# Pi_Block.net
KiCad netlist of a schematic drawn in EAGLE
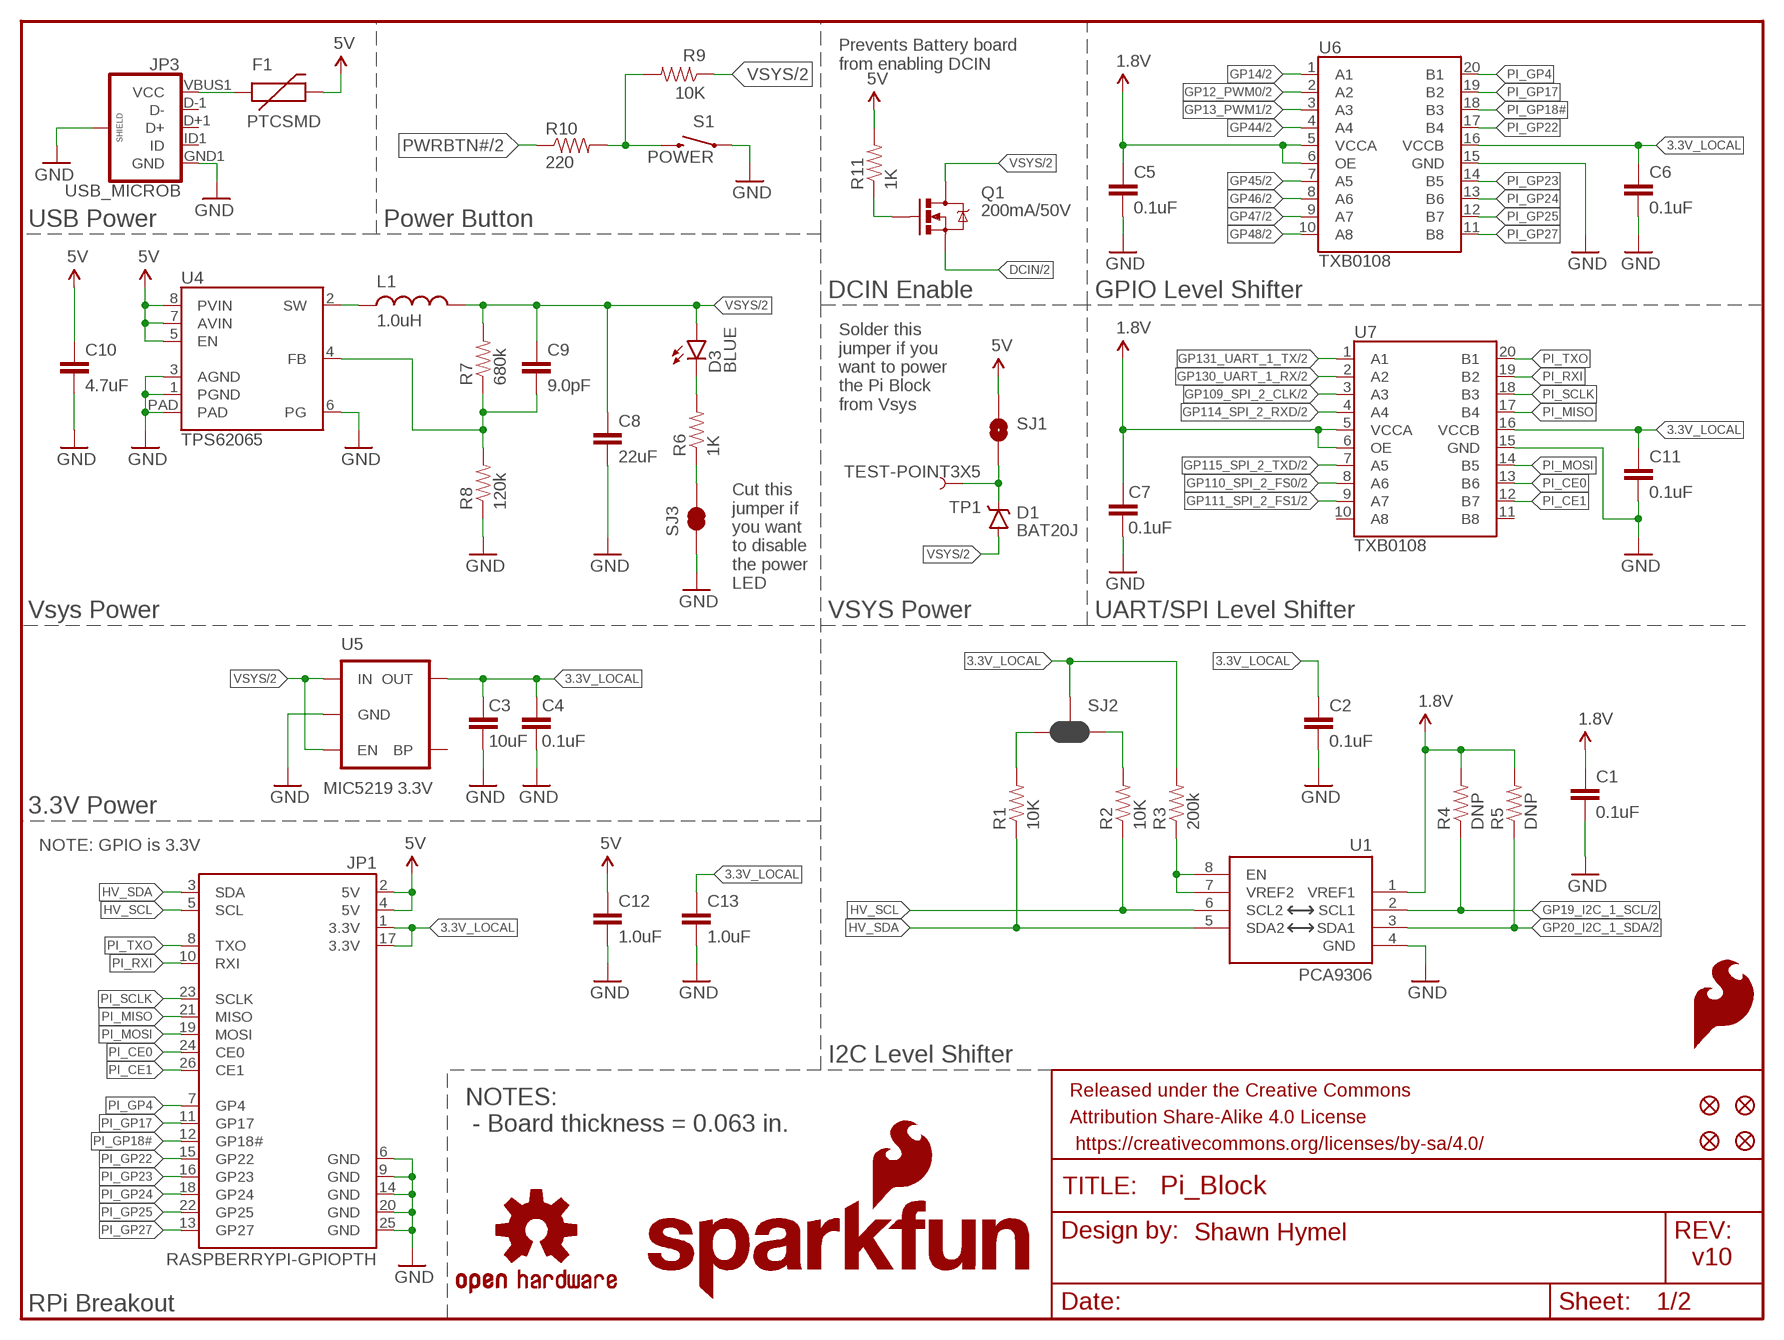
[diagram p0: schematic, sheet 1]
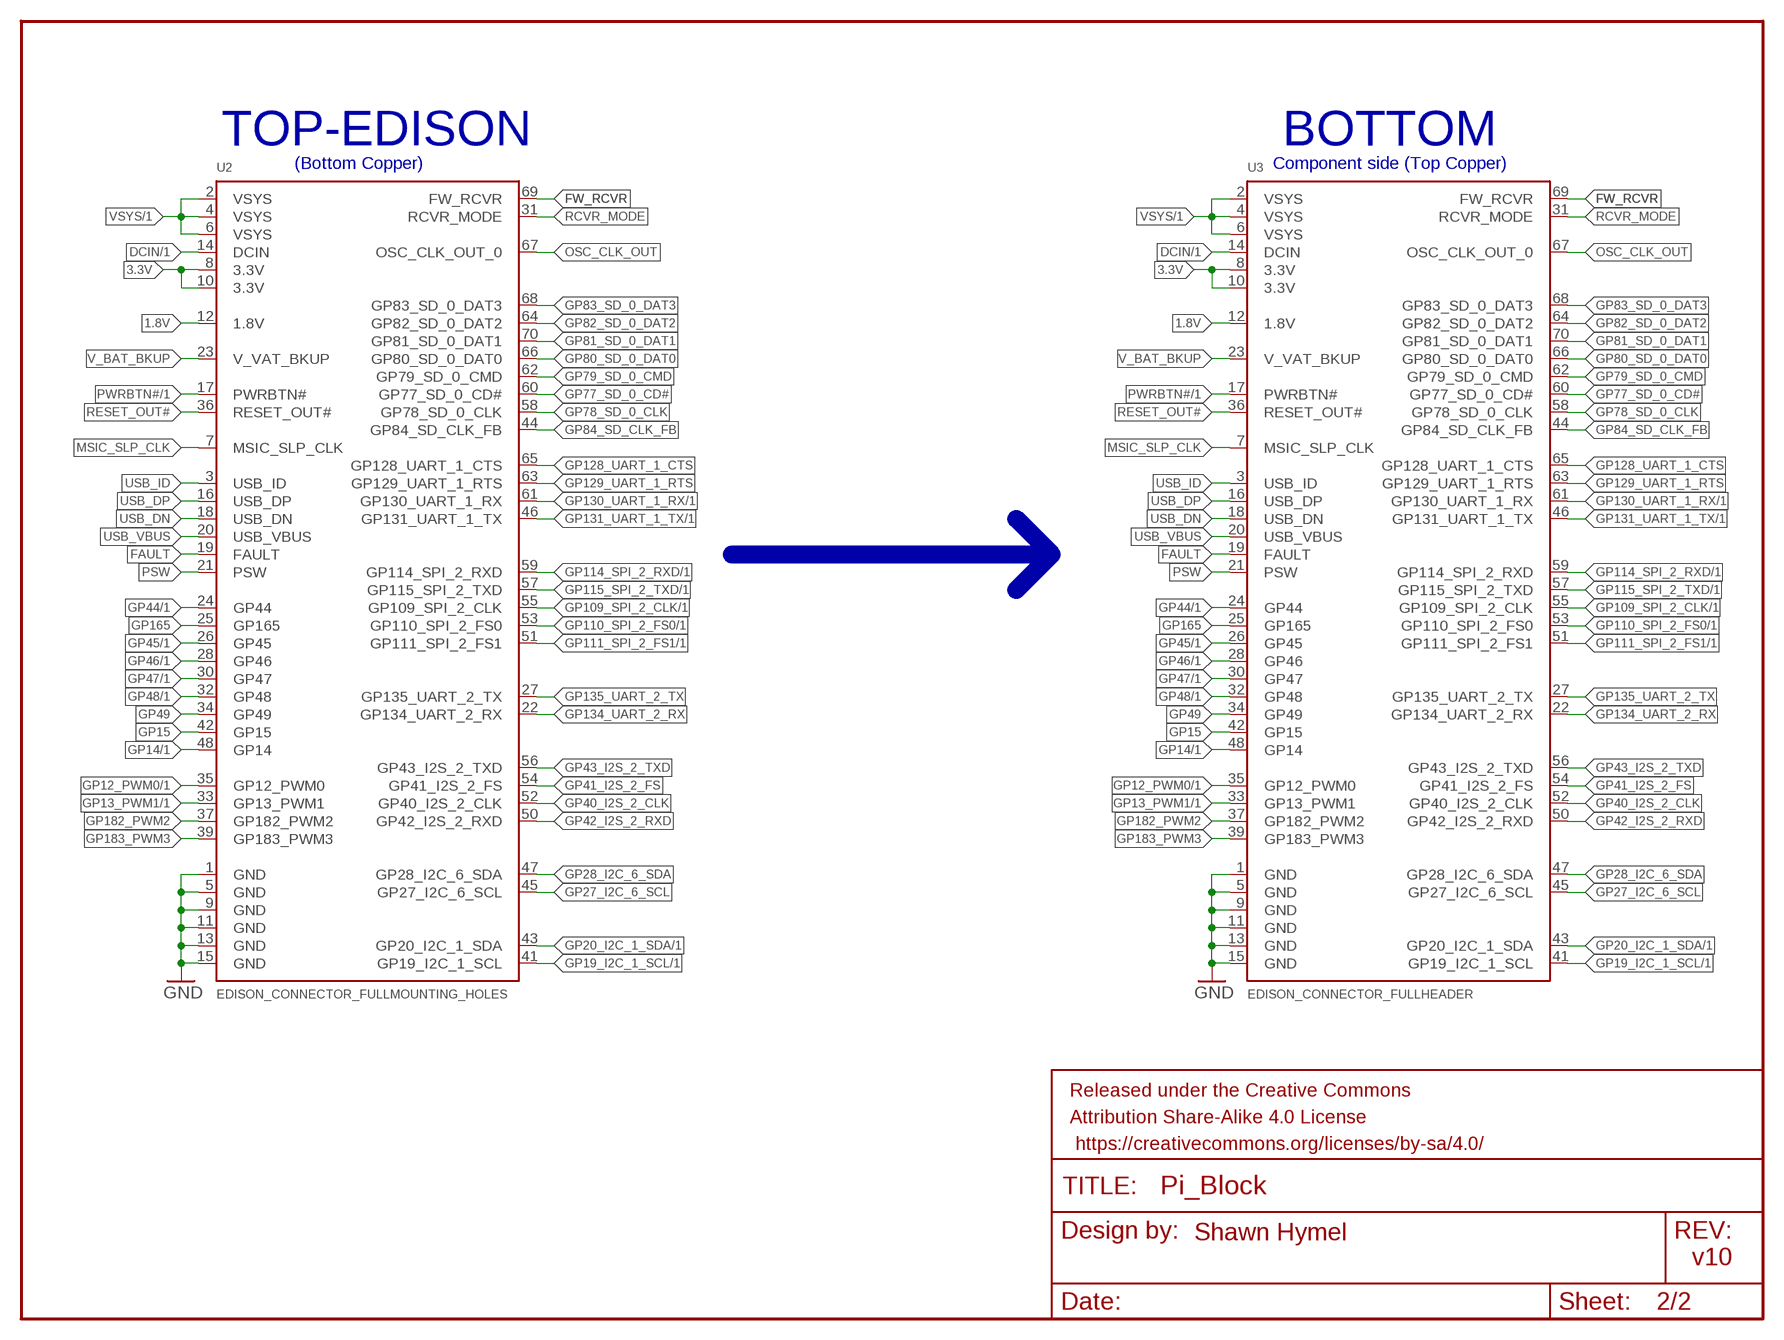
[diagram p1: schematic, sheet 2]

(export (version "E")
  (design (tool "Eeschema 10.0.6"))
  (components
    (comp (ref "FRAME2")
      (value "FRAME-LETTER")
      (footprint "eagle-import:CREATIVE_COMMONS")
      (libsource (lib "eagle-import") (part "FRAME-LETTER"))
    )
    (comp (ref "U2")
      (value "EDISON_CONNECTOR_FULLMOUNTING_HOLES")
      (footprint "eagle-import:EDISON_DAUGHTER")
      (libsource (lib "eagle-import") (part "EDISON_CONNECTOR_FULLMOUNTING_HOLES"))
    )
    (comp (ref "U3")
      (value "EDISON_CONNECTOR_FULLHEADER")
      (footprint "eagle-import:DF40C-70DP-0.4(51)")
      (libsource (lib "eagle-import") (part "EDISON_CONNECTOR_FULLHEADER"))
    )
    (comp (ref "C1")
      (value "0.1uF")
      (footprint "eagle-import:0603-CAP")
      (libsource (lib "eagle-import") (part "0.1UF-25V(+80/-20%)(0603)"))
    )
    (comp (ref "C2")
      (value "0.1uF")
      (footprint "eagle-import:0603-CAP")
      (libsource (lib "eagle-import") (part "0.1UF-25V(+80/-20%)(0603)"))
    )
    (comp (ref "C3")
      (value "10uF")
      (footprint "eagle-import:0805")
      (libsource (lib "eagle-import") (part "CAP0805"))
    )
    (comp (ref "C4")
      (value "0.1uF")
      (footprint "eagle-import:0603-CAP")
      (libsource (lib "eagle-import") (part "0.1UF-25V(+80/-20%)(0603)"))
    )
    (comp (ref "C5")
      (value "0.1uF")
      (footprint "eagle-import:0603-CAP")
      (libsource (lib "eagle-import") (part "0.1UF-25V(+80/-20%)(0603)"))
    )
    (comp (ref "C6")
      (value "0.1uF")
      (footprint "eagle-import:0603-CAP")
      (libsource (lib "eagle-import") (part "0.1UF-25V(+80/-20%)(0603)"))
    )
    (comp (ref "C7")
      (value "0.1uF")
      (footprint "eagle-import:0603-CAP")
      (libsource (lib "eagle-import") (part "0.1UF-25V(+80/-20%)(0603)"))
    )
    (comp (ref "C8")
      (value "22uF")
      (footprint "eagle-import:0805")
      (libsource (lib "eagle-import") (part "22UF-6.3V-20%(0805)"))
    )
    (comp (ref "C9")
      (value "9.0pF")
      (footprint "eagle-import:0603-CAP")
      (libsource (lib "eagle-import") (part "9.0PF-50V-10%(0603)"))
    )
    (comp (ref "C10")
      (value "4.7uF")
      (footprint "eagle-import:0603-CAP")
      (libsource (lib "eagle-import") (part "4.7UF-6.3V-10%(0603)0603"))
    )
    (comp (ref "C11")
      (value "0.1uF")
      (footprint "eagle-import:0603-CAP")
      (libsource (lib "eagle-import") (part "0.1UF-25V(+80/-20%)(0603)"))
    )
    (comp (ref "C12")
      (value "1.0uF")
      (footprint "eagle-import:0603-CAP")
      (libsource (lib "eagle-import") (part "1.0UF-16V-10%(0603)"))
    )
    (comp (ref "C13")
      (value "1.0uF")
      (footprint "eagle-import:0603-CAP")
      (libsource (lib "eagle-import") (part "1.0UF-16V-10%(0603)"))
    )
    (comp (ref "D1")
      (value "BAT20J")
      (footprint "eagle-import:SOD-323")
      (libsource (lib "eagle-import") (part "DIODE-SCHOTTKY-BAT20J"))
    )
    (comp (ref "D3")
      (value "BLUE")
      (footprint "eagle-import:LED-0603")
      (libsource (lib "eagle-import") (part "LED-BLUE0603"))
    )
    (comp (ref "F1")
      (value "PTCSMD")
      (footprint "eagle-import:PTC-1206")
      (libsource (lib "eagle-import") (part "PTCSMD"))
    )
    (comp (ref "FID1")
      (value "FIDUCIAL1X2")
      (footprint "eagle-import:FIDUCIAL-1X2")
      (libsource (lib "eagle-import") (part "FIDUCIAL1X2"))
    )
    (comp (ref "FID2")
      (value "FIDUCIAL1X2")
      (footprint "eagle-import:FIDUCIAL-1X2")
      (libsource (lib "eagle-import") (part "FIDUCIAL1X2"))
    )
    (comp (ref "FID3")
      (value "FIDUCIAL1X2")
      (footprint "eagle-import:FIDUCIAL-1X2")
      (libsource (lib "eagle-import") (part "FIDUCIAL1X2"))
    )
    (comp (ref "FID4")
      (value "FIDUCIAL1X2")
      (footprint "eagle-import:FIDUCIAL-1X2")
      (libsource (lib "eagle-import") (part "FIDUCIAL1X2"))
    )
    (comp (ref "FRAME1")
      (value "FRAME-LETTER")
      (footprint "eagle-import:CREATIVE_COMMONS")
      (libsource (lib "eagle-import") (part "FRAME-LETTER"))
    )
    (comp (ref "FRAME3")
      (value "FRAME-LETTER")
      (footprint "eagle-import:CREATIVE_COMMONS")
      (libsource (lib "eagle-import") (part "FRAME-LETTER"))
    )
    (comp (ref "JP1")
      (value "RASPBERRYPI-GPIOPTH")
      (footprint "eagle-import:2X13-SHROUDED")
      (libsource (lib "eagle-import") (part "RASPBERRYPI-GPIOPTH"))
    )
    (comp (ref "JP3")
      (value "USB_MICROB")
      (footprint "eagle-import:USB-B-MICRO-SMD_V03")
      (libsource (lib "eagle-import") (part "USB_MICROB_PLUGCONN-11752"))
    )
    (comp (ref "L1")
      (value "1.0uH")
      (footprint "eagle-import:INDUCTOR-SRP4020")
      (libsource (lib "eagle-import") (part "INDUCTOR"))
    )
    (comp (ref "LOGO1")
      (value "OSHW-LOGOS")
      (footprint "eagle-import:OSHW-LOGO-S")
      (libsource (lib "eagle-import") (part "OSHW-LOGOS"))
    )
    (comp (ref "LOGO3")
      (value "SFE_LOGO_FLAME.2_INCH")
      (footprint "eagle-import:SFE_LOGO_FLAME_.2")
      (libsource (lib "eagle-import") (part "SFE_LOGO_FLAME.2_INCH"))
    )
    (comp (ref "LOGO4")
      (value "SFE_LOGO_NAME_FLAME.1_INCH")
      (footprint "eagle-import:SFE_LOGO_NAME_FLAME_.1")
      (libsource (lib "eagle-import") (part "SFE_LOGO_NAME_FLAME.1_INCH"))
    )
    (comp (ref "Q1")
      (value "200mA/50V")
      (footprint "eagle-import:SOT23-3")
      (libsource (lib "eagle-import") (part "MOSFET-NCHANNELBSS138"))
    )
    (comp (ref "R1")
      (value "10K")
      (footprint "eagle-import:0603-RES")
      (libsource (lib "eagle-import") (part "10KOHM-1/10W-1%(0603)0603"))
    )
    (comp (ref "R2")
      (value "10K")
      (footprint "eagle-import:0603-RES")
      (libsource (lib "eagle-import") (part "10KOHM-1/10W-1%(0603)0603"))
    )
    (comp (ref "R3")
      (value "200k")
      (footprint "eagle-import:0603-RES")
      (libsource (lib "eagle-import") (part "200KOHM1/10W1%(0603)200K"))
    )
    (comp (ref "R4")
      (value "DNP")
      (footprint "eagle-import:0603-RES")
      (libsource (lib "eagle-import") (part "RESISTOR0603-RES"))
    )
    (comp (ref "R5")
      (value "DNP")
      (footprint "eagle-import:0603-RES")
      (libsource (lib "eagle-import") (part "RESISTOR0603-RES"))
    )
    (comp (ref "R6")
      (value "1K")
      (footprint "eagle-import:0603-RES")
      (libsource (lib "eagle-import") (part "1KOHM-1/10W-1%(0603)"))
    )
    (comp (ref "R7")
      (value "680k")
      (footprint "eagle-import:0603-RES")
      (libsource (lib "eagle-import") (part "RESISTOR0603"))
    )
    (comp (ref "R8")
      (value "120k")
      (footprint "eagle-import:0603-RES")
      (libsource (lib "eagle-import") (part "RESISTOR0603"))
    )
    (comp (ref "R9")
      (value "10K")
      (footprint "eagle-import:0603-RES")
      (libsource (lib "eagle-import") (part "10KOHM-1/10W-1%(0603)0603"))
    )
    (comp (ref "R10")
      (value "220")
      (footprint "eagle-import:0603-RES")
      (libsource (lib "eagle-import") (part "RESISTOR0603"))
    )
    (comp (ref "R11")
      (value "1K")
      (footprint "eagle-import:0603-RES")
      (libsource (lib "eagle-import") (part "1KOHM-1/10W-1%(0603)"))
    )
    (comp (ref "S1")
      (value "POWER")
      (footprint "eagle-import:TACTILE_SWITCH-SMD-RIGHT-ANGLE")
      (libsource (lib "eagle-import") (part "SWITCH-MOMENTARY-2TACTILE-SWITCH-SMD-RIGHT-ANGLE"))
    )
    (comp (ref "SJ1")
      (value "JUMPER-PAD-2-NOYES_SILK")
      (footprint "eagle-import:PAD-JUMPER-2-NO_YES_SILK")
      (libsource (lib "eagle-import") (part "JUMPER-PAD-2-NOYES_SILK"))
    )
    (comp (ref "SJ2")
      (value "JUMPER-PAD-3-NC_BY_PASTE")
      (footprint "eagle-import:PAD-JUMPER-3-NC_BY_PASTE_YES_SILK_FULL_BOX")
      (libsource (lib "eagle-import") (part "JUMPER-PAD-3-NC_BY_PASTE"))
    )
    (comp (ref "SJ3")
      (value "JUMPER-PAD-2-NC_BY_TRACE")
      (footprint "eagle-import:PAD-JUMPER-2-NC_BY_TRACE_YES_SILK")
      (libsource (lib "eagle-import") (part "JUMPER-PAD-2-NC_BY_TRACE"))
    )
    (comp (ref "TP1")
      (value "TEST-POINT3X5")
      (footprint "eagle-import:PAD.03X.05")
      (libsource (lib "eagle-import") (part "TEST-POINT3X5"))
    )
    (comp (ref "U1")
      (value "PCA9306")
      (footprint "eagle-import:PCA9306DC-1_1")
      (libsource (lib "eagle-import") (part "PCA9306PCA9306DC-1{colon}1"))
    )
    (comp (ref "U4")
      (value "TPS62065")
      (footprint "eagle-import:WSON-8-PAD")
      (libsource (lib "eagle-import") (part "TPS62065"))
    )
    (comp (ref "U5")
      (value "MIC5219 3.3V")
      (footprint "eagle-import:SOT23-5")
      (libsource (lib "eagle-import") (part "V_REG_MIC52193.3V"))
    )
    (comp (ref "U6")
      (value "TXB0108")
      (footprint "eagle-import:UFDFN-20")
      (libsource (lib "eagle-import") (part "TXB0108"))
    )
    (comp (ref "U7")
      (value "TXB0108")
      (footprint "eagle-import:UFDFN-20")
      (libsource (lib "eagle-import") (part "TXB0108"))
    )
  )
  (nets
    (net (code "1") (name "1.8V") (class "Default")
      (node (ref "C1") (pin "1") (pinfunction "1_1") (pintype "passive"))
      (node (ref "C5") (pin "1") (pinfunction "1_1") (pintype "passive"))
      (node (ref "C7") (pin "1") (pinfunction "1_1") (pintype "passive"))
      (node (ref "R4") (pin "2") (pinfunction "2_2") (pintype "passive"))
      (node (ref "R5") (pin "2") (pinfunction "2_2") (pintype "passive"))
      (node (ref "U1") (pin "1") (pinfunction "VREF1_1") (pintype "bidirectional"))
      (node (ref "U2") (pin "12") (pinfunction "1.8V_12") (pintype "bidirectional"))
      (node (ref "U3") (pin "12") (pinfunction "1.8V_12") (pintype "bidirectional"))
      (node (ref "U6") (pin "5") (pinfunction "VCCA_5") (pintype "bidirectional"))
      (node (ref "U6") (pin "6") (pinfunction "OE_6") (pintype "bidirectional"))
      (node (ref "U7") (pin "5") (pinfunction "VCCA_5") (pintype "bidirectional"))
      (node (ref "U7") (pin "6") (pinfunction "OE_6") (pintype "bidirectional"))
    )
    (net (code "2") (name "3.3V") (class "Default")
      (node (ref "U2") (pin "10") (pinfunction "3.3V_10") (pintype "bidirectional"))
      (node (ref "U2") (pin "8") (pinfunction "3.3V_8") (pintype "bidirectional"))
      (node (ref "U3") (pin "10") (pinfunction "3.3V_10") (pintype "bidirectional"))
      (node (ref "U3") (pin "8") (pinfunction "3.3V_8") (pintype "bidirectional"))
    )
    (net (code "3") (name "3.3V_LOCAL") (class "Default")
      (node (ref "C11") (pin "1") (pinfunction "1_1") (pintype "passive"))
      (node (ref "C13") (pin "1") (pinfunction "1_1") (pintype "passive"))
      (node (ref "C2") (pin "1") (pinfunction "1_1") (pintype "passive"))
      (node (ref "C3") (pin "1") (pinfunction "1_1") (pintype "passive"))
      (node (ref "C4") (pin "1") (pinfunction "1_1") (pintype "passive"))
      (node (ref "C6") (pin "1") (pinfunction "1_1") (pintype "passive"))
      (node (ref "JP1") (pin "1") (pinfunction "3.3V_1") (pintype "power_in"))
      (node (ref "JP1") (pin "17") (pinfunction "3.3V_17") (pintype "power_in"))
      (node (ref "R3") (pin "2") (pinfunction "2_2") (pintype "passive"))
      (node (ref "SJ2") (pin "2") (pinfunction "2_2") (pintype "passive"))
      (node (ref "U5") (pin "5") (pinfunction "OUT_5") (pintype "passive"))
      (node (ref "U6") (pin "16") (pinfunction "VCCB_16") (pintype "bidirectional"))
      (node (ref "U7") (pin "16") (pinfunction "VCCB_16") (pintype "bidirectional"))
    )
    (net (code "4") (name "5V") (class "Default")
      (node (ref "C10") (pin "1") (pinfunction "1_1") (pintype "passive"))
      (node (ref "C12") (pin "1") (pinfunction "1_1") (pintype "passive"))
      (node (ref "F1") (pin "2") (pinfunction "2_2") (pintype "bidirectional"))
      (node (ref "JP1") (pin "2") (pinfunction "5V_2") (pintype "power_in"))
      (node (ref "JP1") (pin "4") (pinfunction "5V_4") (pintype "power_in"))
      (node (ref "R11") (pin "2") (pinfunction "2_2") (pintype "passive"))
      (node (ref "SJ1") (pin "1") (pinfunction "1_1") (pintype "passive"))
      (node (ref "U4") (pin "5") (pinfunction "EN_5") (pintype "bidirectional"))
      (node (ref "U4") (pin "7") (pinfunction "AVIN_7") (pintype "bidirectional"))
      (node (ref "U4") (pin "8") (pinfunction "PVIN_8") (pintype "bidirectional"))
    )
    (net (code "5") (name "DCIN") (class "Default")
      (node (ref "Q1") (pin "2") (pinfunction "S_2") (pintype "passive"))
      (node (ref "U2") (pin "14") (pinfunction "DCIN_14") (pintype "bidirectional"))
      (node (ref "U3") (pin "14") (pinfunction "DCIN_14") (pintype "bidirectional"))
    )
    (net (code "6") (name "FAULT") (class "Default")
      (node (ref "U2") (pin "19") (pinfunction "FAULT_19") (pintype "bidirectional"))
      (node (ref "U3") (pin "19") (pinfunction "FAULT_19") (pintype "bidirectional"))
    )
    (net (code "7") (name "FW_RCVR") (class "Default")
      (node (ref "U2") (pin "69") (pinfunction "FW_RCVR_69") (pintype "bidirectional"))
      (node (ref "U3") (pin "69") (pinfunction "FW_RCVR_69") (pintype "bidirectional"))
    )
    (net (code "8") (name "GND") (class "Default")
      (node (ref "C1") (pin "2") (pinfunction "2_2") (pintype "passive"))
      (node (ref "C10") (pin "2") (pinfunction "2_2") (pintype "passive"))
      (node (ref "C11") (pin "2") (pinfunction "2_2") (pintype "passive"))
      (node (ref "C12") (pin "2") (pinfunction "2_2") (pintype "passive"))
      (node (ref "C13") (pin "2") (pinfunction "2_2") (pintype "passive"))
      (node (ref "C2") (pin "2") (pinfunction "2_2") (pintype "passive"))
      (node (ref "C3") (pin "2") (pinfunction "2_2") (pintype "passive"))
      (node (ref "C4") (pin "2") (pinfunction "2_2") (pintype "passive"))
      (node (ref "C5") (pin "2") (pinfunction "2_2") (pintype "passive"))
      (node (ref "C6") (pin "2") (pinfunction "2_2") (pintype "passive"))
      (node (ref "C7") (pin "2") (pinfunction "2_2") (pintype "passive"))
      (node (ref "C8") (pin "2") (pinfunction "2_2") (pintype "passive"))
      (node (ref "JP1") (pin "14") (pinfunction "GND_14") (pintype "power_in"))
      (node (ref "JP1") (pin "20") (pinfunction "GND_20") (pintype "power_in"))
      (node (ref "JP1") (pin "25") (pinfunction "GND_25") (pintype "power_in"))
      (node (ref "JP1") (pin "6") (pinfunction "GND_6") (pintype "power_in"))
      (node (ref "JP1") (pin "9") (pinfunction "GND_9") (pintype "power_in"))
      (node (ref "JP3") (pin "GND1") (pinfunction "GND_GND1") (pintype "bidirectional"))
      (node (ref "JP3") (pin "SHIELD1") (pinfunction "SHIELD_SHIELD1") (pintype "bidirectional"))
      (node (ref "JP3") (pin "SHIELD2") (pinfunction "SHIELD_SHIELD2") (pintype "bidirectional"))
      (node (ref "JP3") (pin "SHIELD3") (pinfunction "SHIELD_SHIELD3") (pintype "bidirectional"))
      (node (ref "R8") (pin "1") (pinfunction "1_1") (pintype "passive"))
      (node (ref "S1") (pin "1") (pinfunction "1_1") (pintype "passive"))
      (node (ref "SJ3") (pin "1") (pinfunction "1_1") (pintype "passive"))
      (node (ref "U1") (pin "4") (pinfunction "GND_4") (pintype "bidirectional"))
      (node (ref "U2") (pin "1") (pinfunction "GND_1") (pintype "bidirectional"))
      (node (ref "U2") (pin "11") (pinfunction "GND_11") (pintype "bidirectional"))
      (node (ref "U2") (pin "13") (pinfunction "GND_13") (pintype "bidirectional"))
      (node (ref "U2") (pin "15") (pinfunction "GND_15") (pintype "bidirectional"))
      (node (ref "U2") (pin "5") (pinfunction "GND_5") (pintype "bidirectional"))
      (node (ref "U2") (pin "9") (pinfunction "GND_9") (pintype "bidirectional"))
      (node (ref "U3") (pin "1") (pinfunction "GND_1") (pintype "bidirectional"))
      (node (ref "U3") (pin "11") (pinfunction "GND_11") (pintype "bidirectional"))
      (node (ref "U3") (pin "13") (pinfunction "GND_13") (pintype "bidirectional"))
      (node (ref "U3") (pin "15") (pinfunction "GND_15") (pintype "bidirectional"))
      (node (ref "U3") (pin "5") (pinfunction "GND_5") (pintype "bidirectional"))
      (node (ref "U3") (pin "9") (pinfunction "GND_9") (pintype "bidirectional"))
      (node (ref "U4") (pin "1") (pinfunction "PGND_1") (pintype "bidirectional"))
      (node (ref "U4") (pin "3") (pinfunction "AGND_3") (pintype "bidirectional"))
      (node (ref "U4") (pin "6") (pinfunction "PG_6") (pintype "bidirectional"))
      (node (ref "U4") (pin "PAD") (pinfunction "PAD_PAD") (pintype "bidirectional"))
      (node (ref "U5") (pin "2") (pinfunction "GND_2") (pintype "input"))
      (node (ref "U6") (pin "15") (pinfunction "GND_15") (pintype "bidirectional"))
      (node (ref "U7") (pin "15") (pinfunction "GND_15") (pintype "bidirectional"))
    )
    (net (code "9") (name "GP12_PWM0") (class "Default")
      (node (ref "U2") (pin "35") (pinfunction "GP12_PWM0_35") (pintype "bidirectional"))
      (node (ref "U3") (pin "35") (pinfunction "GP12_PWM0_35") (pintype "bidirectional"))
      (node (ref "U6") (pin "2") (pinfunction "A2_2") (pintype "bidirectional"))
    )
    (net (code "10") (name "GP13_PWM1") (class "Default")
      (node (ref "U2") (pin "33") (pinfunction "GP13_PWM1_33") (pintype "bidirectional"))
      (node (ref "U3") (pin "33") (pinfunction "GP13_PWM1_33") (pintype "bidirectional"))
      (node (ref "U6") (pin "3") (pinfunction "A3_3") (pintype "bidirectional"))
    )
    (net (code "11") (name "GP14") (class "Default")
      (node (ref "U2") (pin "48") (pinfunction "GP14_48") (pintype "bidirectional"))
      (node (ref "U3") (pin "48") (pinfunction "GP14_48") (pintype "bidirectional"))
      (node (ref "U6") (pin "1") (pinfunction "A1_1") (pintype "bidirectional"))
    )
    (net (code "12") (name "GP15") (class "Default")
      (node (ref "U2") (pin "42") (pinfunction "GP15_42") (pintype "bidirectional"))
      (node (ref "U3") (pin "42") (pinfunction "GP15_42") (pintype "bidirectional"))
    )
    (net (code "13") (name "GP19_I2C_1_SCL") (class "Default")
      (node (ref "R4") (pin "1") (pinfunction "1_1") (pintype "passive"))
      (node (ref "U1") (pin "2") (pinfunction "SCL1_2") (pintype "bidirectional"))
      (node (ref "U2") (pin "41") (pinfunction "GP19_I2C_1_SCL_41") (pintype "bidirectional"))
      (node (ref "U3") (pin "41") (pinfunction "GP19_I2C_1_SCL_41") (pintype "bidirectional"))
    )
    (net (code "14") (name "GP20_I2C_1_SDA") (class "Default")
      (node (ref "R5") (pin "1") (pinfunction "1_1") (pintype "passive"))
      (node (ref "U1") (pin "3") (pinfunction "SDA1_3") (pintype "bidirectional"))
      (node (ref "U2") (pin "43") (pinfunction "GP20_I2C_1_SDA_43") (pintype "bidirectional"))
      (node (ref "U3") (pin "43") (pinfunction "GP20_I2C_1_SDA_43") (pintype "bidirectional"))
    )
    (net (code "15") (name "GP27_I2C_6_SCL") (class "Default")
      (node (ref "U2") (pin "45") (pinfunction "GP27_I2C_6_SCL_45") (pintype "bidirectional"))
      (node (ref "U3") (pin "45") (pinfunction "GP27_I2C_6_SCL_45") (pintype "bidirectional"))
    )
    (net (code "16") (name "GP28_I2C_6_SDA") (class "Default")
      (node (ref "U2") (pin "47") (pinfunction "GP28_I2C_6_SDA_47") (pintype "bidirectional"))
      (node (ref "U3") (pin "47") (pinfunction "GP28_I2C_6_SDA_47") (pintype "bidirectional"))
    )
    (net (code "17") (name "GP40_I2S_2_CLK") (class "Default")
      (node (ref "U2") (pin "52") (pinfunction "GP40_I2S_2_CLK_52") (pintype "bidirectional"))
      (node (ref "U3") (pin "52") (pinfunction "GP40_I2S_2_CLK_52") (pintype "bidirectional"))
    )
    (net (code "18") (name "GP41_I2S_2_FS") (class "Default")
      (node (ref "U2") (pin "54") (pinfunction "GP41_I2S_2_FS_54") (pintype "bidirectional"))
      (node (ref "U3") (pin "54") (pinfunction "GP41_I2S_2_FS_54") (pintype "bidirectional"))
    )
    (net (code "19") (name "GP42_I2S_2_RXD") (class "Default")
      (node (ref "U2") (pin "50") (pinfunction "GP42_I2S_2_RXD_50") (pintype "bidirectional"))
      (node (ref "U3") (pin "50") (pinfunction "GP42_I2S_2_RXD_50") (pintype "bidirectional"))
    )
    (net (code "20") (name "GP43_I2S_2_TXD") (class "Default")
      (node (ref "U2") (pin "56") (pinfunction "GP43_I2S_2_TXD_56") (pintype "bidirectional"))
      (node (ref "U3") (pin "56") (pinfunction "GP43_I2S_2_TXD_56") (pintype "bidirectional"))
    )
    (net (code "21") (name "GP44") (class "Default")
      (node (ref "U2") (pin "24") (pinfunction "GP44_24") (pintype "bidirectional"))
      (node (ref "U3") (pin "24") (pinfunction "GP44_24") (pintype "bidirectional"))
      (node (ref "U6") (pin "4") (pinfunction "A4_4") (pintype "bidirectional"))
    )
    (net (code "22") (name "GP45") (class "Default")
      (node (ref "U2") (pin "26") (pinfunction "GP45_26") (pintype "bidirectional"))
      (node (ref "U3") (pin "26") (pinfunction "GP45_26") (pintype "bidirectional"))
      (node (ref "U6") (pin "7") (pinfunction "A5_7") (pintype "bidirectional"))
    )
    (net (code "23") (name "GP46") (class "Default")
      (node (ref "U2") (pin "28") (pinfunction "GP46_28") (pintype "bidirectional"))
      (node (ref "U3") (pin "28") (pinfunction "GP46_28") (pintype "bidirectional"))
      (node (ref "U6") (pin "8") (pinfunction "A6_8") (pintype "bidirectional"))
    )
    (net (code "24") (name "GP47") (class "Default")
      (node (ref "U2") (pin "30") (pinfunction "GP47_30") (pintype "bidirectional"))
      (node (ref "U3") (pin "30") (pinfunction "GP47_30") (pintype "bidirectional"))
      (node (ref "U6") (pin "9") (pinfunction "A7_9") (pintype "bidirectional"))
    )
    (net (code "25") (name "GP48") (class "Default")
      (node (ref "U2") (pin "32") (pinfunction "GP48_32") (pintype "bidirectional"))
      (node (ref "U3") (pin "32") (pinfunction "GP48_32") (pintype "bidirectional"))
      (node (ref "U6") (pin "10") (pinfunction "A8_10") (pintype "bidirectional"))
    )
    (net (code "26") (name "GP49") (class "Default")
      (node (ref "U2") (pin "34") (pinfunction "GP49_34") (pintype "bidirectional"))
      (node (ref "U3") (pin "34") (pinfunction "GP49_34") (pintype "bidirectional"))
    )
    (net (code "27") (name "GP77_SD_0_CD#") (class "Default")
      (node (ref "U2") (pin "60") (pinfunction "GP77_SD_0_CD#_60") (pintype "bidirectional"))
      (node (ref "U3") (pin "60") (pinfunction "GP77_SD_0_CD#_60") (pintype "bidirectional"))
    )
    (net (code "28") (name "GP78_SD_0_CLK") (class "Default")
      (node (ref "U2") (pin "58") (pinfunction "GP78_SD_0_CLK_58") (pintype "bidirectional"))
      (node (ref "U3") (pin "58") (pinfunction "GP78_SD_0_CLK_58") (pintype "bidirectional"))
    )
    (net (code "29") (name "GP79_SD_0_CMD") (class "Default")
      (node (ref "U2") (pin "62") (pinfunction "GP79_SD_0_CMD_62") (pintype "bidirectional"))
      (node (ref "U3") (pin "62") (pinfunction "GP79_SD_0_CMD_62") (pintype "bidirectional"))
    )
    (net (code "30") (name "GP80_SD_0_DAT0") (class "Default")
      (node (ref "U2") (pin "66") (pinfunction "GP80_SD_0_DAT0_66") (pintype "bidirectional"))
      (node (ref "U3") (pin "66") (pinfunction "GP80_SD_0_DAT0_66") (pintype "bidirectional"))
    )
    (net (code "31") (name "GP81_SD_0_DAT1") (class "Default")
      (node (ref "U2") (pin "70") (pinfunction "GP81_SD_0_DAT1_70") (pintype "bidirectional"))
      (node (ref "U3") (pin "70") (pinfunction "GP81_SD_0_DAT1_70") (pintype "bidirectional"))
    )
    (net (code "32") (name "GP82_SD_0_DAT2") (class "Default")
      (node (ref "U2") (pin "64") (pinfunction "GP82_SD_0_DAT2_64") (pintype "bidirectional"))
      (node (ref "U3") (pin "64") (pinfunction "GP82_SD_0_DAT2_64") (pintype "bidirectional"))
    )
    (net (code "33") (name "GP83_SD_0_DAT3") (class "Default")
      (node (ref "U2") (pin "68") (pinfunction "GP83_SD_0_DAT3_68") (pintype "bidirectional"))
      (node (ref "U3") (pin "68") (pinfunction "GP83_SD_0_DAT3_68") (pintype "bidirectional"))
    )
    (net (code "34") (name "GP84_SD_CLK_FB") (class "Default")
      (node (ref "U2") (pin "44") (pinfunction "GP84_SD_CLK_FB_44") (pintype "bidirectional"))
      (node (ref "U3") (pin "44") (pinfunction "GP84_SD_CLK_FB_44") (pintype "bidirectional"))
    )
    (net (code "35") (name "GP109_SPI_2_CLK") (class "Default")
      (node (ref "U2") (pin "55") (pinfunction "GP109_SPI_2_CLK_55") (pintype "bidirectional"))
      (node (ref "U3") (pin "55") (pinfunction "GP109_SPI_2_CLK_55") (pintype "bidirectional"))
      (node (ref "U7") (pin "3") (pinfunction "A3_3") (pintype "bidirectional"))
    )
    (net (code "36") (name "GP110_SPI_2_FS0") (class "Default")
      (node (ref "U2") (pin "53") (pinfunction "GP110_SPI_2_FS0_53") (pintype "bidirectional"))
      (node (ref "U3") (pin "53") (pinfunction "GP110_SPI_2_FS0_53") (pintype "bidirectional"))
      (node (ref "U7") (pin "8") (pinfunction "A6_8") (pintype "bidirectional"))
    )
    (net (code "37") (name "GP111_SPI_2_FS1") (class "Default")
      (node (ref "U2") (pin "51") (pinfunction "GP111_SPI_2_FS1_51") (pintype "bidirectional"))
      (node (ref "U3") (pin "51") (pinfunction "GP111_SPI_2_FS1_51") (pintype "bidirectional"))
      (node (ref "U7") (pin "9") (pinfunction "A7_9") (pintype "bidirectional"))
    )
    (net (code "38") (name "GP114_SPI_2_RXD") (class "Default")
      (node (ref "U2") (pin "59") (pinfunction "GP114_SPI_2_RXD_59") (pintype "bidirectional"))
      (node (ref "U3") (pin "59") (pinfunction "GP114_SPI_2_RXD_59") (pintype "bidirectional"))
      (node (ref "U7") (pin "4") (pinfunction "A4_4") (pintype "bidirectional"))
    )
    (net (code "39") (name "GP115_SPI_2_TXD") (class "Default")
      (node (ref "U2") (pin "57") (pinfunction "GP115_SPI_2_TXD_57") (pintype "bidirectional"))
      (node (ref "U3") (pin "57") (pinfunction "GP115_SPI_2_TXD_57") (pintype "bidirectional"))
      (node (ref "U7") (pin "7") (pinfunction "A5_7") (pintype "bidirectional"))
    )
    (net (code "40") (name "GP128_UART_1_CTS") (class "Default")
      (node (ref "U2") (pin "65") (pinfunction "GP128_UART_1_CTS_65") (pintype "bidirectional"))
      (node (ref "U3") (pin "65") (pinfunction "GP128_UART_1_CTS_65") (pintype "bidirectional"))
    )
    (net (code "41") (name "GP129_UART_1_RTS") (class "Default")
      (node (ref "U2") (pin "63") (pinfunction "GP129_UART_1_RTS_63") (pintype "bidirectional"))
      (node (ref "U3") (pin "63") (pinfunction "GP129_UART_1_RTS_63") (pintype "bidirectional"))
    )
    (net (code "42") (name "GP130_UART_1_RX") (class "Default")
      (node (ref "U2") (pin "61") (pinfunction "GP130_UART_1_RX_61") (pintype "bidirectional"))
      (node (ref "U3") (pin "61") (pinfunction "GP130_UART_1_RX_61") (pintype "bidirectional"))
      (node (ref "U7") (pin "2") (pinfunction "A2_2") (pintype "bidirectional"))
    )
    (net (code "43") (name "GP131_UART_1_TX") (class "Default")
      (node (ref "U2") (pin "46") (pinfunction "GP131_UART_1_TX_46") (pintype "bidirectional"))
      (node (ref "U3") (pin "46") (pinfunction "GP131_UART_1_TX_46") (pintype "bidirectional"))
      (node (ref "U7") (pin "1") (pinfunction "A1_1") (pintype "bidirectional"))
    )
    (net (code "44") (name "GP134_UART_2_RX") (class "Default")
      (node (ref "U2") (pin "22") (pinfunction "GP134_UART_2_RX_22") (pintype "bidirectional"))
      (node (ref "U3") (pin "22") (pinfunction "GP134_UART_2_RX_22") (pintype "bidirectional"))
    )
    (net (code "45") (name "GP135_UART_2_TX") (class "Default")
      (node (ref "U2") (pin "27") (pinfunction "GP135_UART_2_TX_27") (pintype "bidirectional"))
      (node (ref "U3") (pin "27") (pinfunction "GP135_UART_2_TX_27") (pintype "bidirectional"))
    )
    (net (code "46") (name "GP165") (class "Default")
      (node (ref "U2") (pin "25") (pinfunction "GP165_25") (pintype "bidirectional"))
      (node (ref "U3") (pin "25") (pinfunction "GP165_25") (pintype "bidirectional"))
    )
    (net (code "47") (name "GP182_PWM2") (class "Default")
      (node (ref "U2") (pin "37") (pinfunction "GP182_PWM2_37") (pintype "bidirectional"))
      (node (ref "U3") (pin "37") (pinfunction "GP182_PWM2_37") (pintype "bidirectional"))
    )
    (net (code "48") (name "GP183_PWM3") (class "Default")
      (node (ref "U2") (pin "39") (pinfunction "GP183_PWM3_39") (pintype "bidirectional"))
      (node (ref "U3") (pin "39") (pinfunction "GP183_PWM3_39") (pintype "bidirectional"))
    )
    (net (code "49") (name "HV_SCL") (class "Default")
      (node (ref "JP1") (pin "5") (pinfunction "SCL_5") (pintype "bidirectional"))
      (node (ref "R2") (pin "1") (pinfunction "1_1") (pintype "passive"))
      (node (ref "U1") (pin "6") (pinfunction "SCL2_6") (pintype "bidirectional"))
    )
    (net (code "50") (name "HV_SDA") (class "Default")
      (node (ref "JP1") (pin "3") (pinfunction "SDA_3") (pintype "bidirectional"))
      (node (ref "R1") (pin "1") (pinfunction "1_1") (pintype "passive"))
      (node (ref "U1") (pin "5") (pinfunction "SDA2_5") (pintype "bidirectional"))
    )
    (net (code "51") (name "MSIC_SLP_CLK") (class "Default")
      (node (ref "U2") (pin "7") (pinfunction "MSIC_SLP_CLK_7") (pintype "bidirectional"))
      (node (ref "U3") (pin "7") (pinfunction "MSIC_SLP_CLK_7") (pintype "bidirectional"))
    )
    (net (code "52") (name "Net-(D3-PadC)") (class "Default")
      (node (ref "D3") (pin "C") (pinfunction "C_C") (pintype "passive"))
      (node (ref "R6") (pin "2") (pinfunction "2_2") (pintype "passive"))
    )
    (net (code "53") (name "Net-(JP3-VCC)") (class "Default")
      (node (ref "F1") (pin "1") (pinfunction "1_1") (pintype "bidirectional"))
      (node (ref "JP3") (pin "VBUS1") (pinfunction "VCC_VBUS1") (pintype "bidirectional"))
    )
    (net (code "54") (name "Net-(L1-1)") (class "Default")
      (node (ref "L1") (pin "P$1") (pinfunction "1_P$1") (pintype "passive"))
      (node (ref "U4") (pin "2") (pinfunction "SW_2") (pintype "bidirectional"))
    )
    (net (code "55") (name "Net-(Q1-G)") (class "Default")
      (node (ref "Q1") (pin "1") (pinfunction "G_1") (pintype "passive"))
      (node (ref "R11") (pin "1") (pinfunction "1_1") (pintype "passive"))
    )
    (net (code "56") (name "Net-(R1-Pad2)") (class "Default")
      (node (ref "R1") (pin "2") (pinfunction "2_2") (pintype "passive"))
      (node (ref "SJ2") (pin "3") (pinfunction "3_3") (pintype "passive"))
    )
    (net (code "57") (name "Net-(R2-Pad2)") (class "Default")
      (node (ref "R2") (pin "2") (pinfunction "2_2") (pintype "passive"))
      (node (ref "SJ2") (pin "1") (pinfunction "1_1") (pintype "passive"))
    )
    (net (code "58") (name "Net-(R6-Pad1)") (class "Default")
      (node (ref "R6") (pin "1") (pinfunction "1_1") (pintype "passive"))
      (node (ref "SJ3") (pin "2") (pinfunction "2_2") (pintype "passive"))
    )
    (net (code "59") (name "Net-(R10-Pad2)") (class "Default")
      (node (ref "R10") (pin "2") (pinfunction "2_2") (pintype "passive"))
      (node (ref "R9") (pin "2") (pinfunction "2_2") (pintype "passive"))
      (node (ref "S1") (pin "2") (pinfunction "2_2") (pintype "passive"))
    )
    (net (code "60") (name "Net-(TP1-1)") (class "Default")
      (node (ref "D1") (pin "C") (pinfunction "C_C") (pintype "passive"))
      (node (ref "SJ1") (pin "2") (pinfunction "2_2") (pintype "passive"))
      (node (ref "TP1") (pin "P$1") (pinfunction "1_P$1") (pintype "bidirectional"))
    )
    (net (code "61") (name "Net-(U1-EN)") (class "Default")
      (node (ref "R3") (pin "1") (pinfunction "1_1") (pintype "passive"))
      (node (ref "U1") (pin "7") (pinfunction "VREF2_7") (pintype "bidirectional"))
      (node (ref "U1") (pin "8") (pinfunction "EN_8") (pintype "bidirectional"))
    )
    (net (code "62") (name "Net-(U4-FB)") (class "Default")
      (node (ref "C9") (pin "2") (pinfunction "2_2") (pintype "passive"))
      (node (ref "R7") (pin "1") (pinfunction "1_1") (pintype "passive"))
      (node (ref "R8") (pin "2") (pinfunction "2_2") (pintype "passive"))
      (node (ref "U4") (pin "4") (pinfunction "FB_4") (pintype "bidirectional"))
    )
    (net (code "63") (name "OSC_CLK_OUT") (class "Default")
      (node (ref "U2") (pin "67") (pinfunction "OSC_CLK_OUT_0_67") (pintype "bidirectional"))
      (node (ref "U3") (pin "67") (pinfunction "OSC_CLK_OUT_0_67") (pintype "bidirectional"))
    )
    (net (code "64") (name "PI_CE0") (class "Default")
      (node (ref "JP1") (pin "24") (pinfunction "CE0_24") (pintype "output"))
      (node (ref "U7") (pin "13") (pinfunction "B6_13") (pintype "bidirectional"))
    )
    (net (code "65") (name "PI_CE1") (class "Default")
      (node (ref "JP1") (pin "26") (pinfunction "CE1_26") (pintype "output"))
      (node (ref "U7") (pin "12") (pinfunction "B7_12") (pintype "bidirectional"))
    )
    (net (code "66") (name "PI_GP4") (class "Default")
      (node (ref "JP1") (pin "7") (pinfunction "GP4_7") (pintype "bidirectional"))
      (node (ref "U6") (pin "20") (pinfunction "B1_20") (pintype "bidirectional"))
    )
    (net (code "67") (name "PI_GP17") (class "Default")
      (node (ref "JP1") (pin "11") (pinfunction "GP17_11") (pintype "bidirectional"))
      (node (ref "U6") (pin "19") (pinfunction "B2_19") (pintype "bidirectional"))
    )
    (net (code "68") (name "PI_GP18#") (class "Default")
      (node (ref "JP1") (pin "12") (pinfunction "GP18#_12") (pintype "bidirectional"))
      (node (ref "U6") (pin "18") (pinfunction "B3_18") (pintype "bidirectional"))
    )
    (net (code "69") (name "PI_GP22") (class "Default")
      (node (ref "JP1") (pin "15") (pinfunction "GP22_15") (pintype "bidirectional"))
      (node (ref "U6") (pin "17") (pinfunction "B4_17") (pintype "bidirectional"))
    )
    (net (code "70") (name "PI_GP23") (class "Default")
      (node (ref "JP1") (pin "16") (pinfunction "GP23_16") (pintype "bidirectional"))
      (node (ref "U6") (pin "14") (pinfunction "B5_14") (pintype "bidirectional"))
    )
    (net (code "71") (name "PI_GP24") (class "Default")
      (node (ref "JP1") (pin "18") (pinfunction "GP24_18") (pintype "bidirectional"))
      (node (ref "U6") (pin "13") (pinfunction "B6_13") (pintype "bidirectional"))
    )
    (net (code "72") (name "PI_GP25") (class "Default")
      (node (ref "JP1") (pin "22") (pinfunction "GP25_22") (pintype "bidirectional"))
      (node (ref "U6") (pin "12") (pinfunction "B7_12") (pintype "bidirectional"))
    )
    (net (code "73") (name "PI_GP27") (class "Default")
      (node (ref "JP1") (pin "13") (pinfunction "GP27_13") (pintype "bidirectional"))
      (node (ref "U6") (pin "11") (pinfunction "B8_11") (pintype "bidirectional"))
    )
    (net (code "74") (name "PI_MISO") (class "Default")
      (node (ref "JP1") (pin "21") (pinfunction "MISO_21") (pintype "input"))
      (node (ref "U7") (pin "17") (pinfunction "B4_17") (pintype "bidirectional"))
    )
    (net (code "75") (name "PI_MOSI") (class "Default")
      (node (ref "JP1") (pin "19") (pinfunction "MOSI_19") (pintype "output"))
      (node (ref "U7") (pin "14") (pinfunction "B5_14") (pintype "bidirectional"))
    )
    (net (code "76") (name "PI_RXI") (class "Default")
      (node (ref "JP1") (pin "10") (pinfunction "RXI_10") (pintype "input"))
      (node (ref "U7") (pin "19") (pinfunction "B2_19") (pintype "bidirectional"))
    )
    (net (code "77") (name "PI_SCLK") (class "Default")
      (node (ref "JP1") (pin "23") (pinfunction "SCLK_23") (pintype "output"))
      (node (ref "U7") (pin "18") (pinfunction "B3_18") (pintype "bidirectional"))
    )
    (net (code "78") (name "PI_TXO") (class "Default")
      (node (ref "JP1") (pin "8") (pinfunction "TXO_8") (pintype "output"))
      (node (ref "U7") (pin "20") (pinfunction "B1_20") (pintype "bidirectional"))
    )
    (net (code "79") (name "PSW") (class "Default")
      (node (ref "U2") (pin "21") (pinfunction "PSW_21") (pintype "bidirectional"))
      (node (ref "U3") (pin "21") (pinfunction "PSW_21") (pintype "bidirectional"))
    )
    (net (code "80") (name "PWRBTN#") (class "Default")
      (node (ref "R10") (pin "1") (pinfunction "1_1") (pintype "passive"))
      (node (ref "U2") (pin "17") (pinfunction "PWRBTN#_17") (pintype "bidirectional"))
      (node (ref "U3") (pin "17") (pinfunction "PWRBTN#_17") (pintype "bidirectional"))
    )
    (net (code "81") (name "RCVR_MODE") (class "Default")
      (node (ref "U2") (pin "31") (pinfunction "RCVR_MODE_31") (pintype "bidirectional"))
      (node (ref "U3") (pin "31") (pinfunction "RCVR_MODE_31") (pintype "bidirectional"))
    )
    (net (code "82") (name "RESET_OUT#") (class "Default")
      (node (ref "U2") (pin "36") (pinfunction "RESET_OUT#_36") (pintype "bidirectional"))
      (node (ref "U3") (pin "36") (pinfunction "RESET_OUT#_36") (pintype "bidirectional"))
    )
    (net (code "83") (name "USB_DN") (class "Default")
      (node (ref "U2") (pin "18") (pinfunction "USB_DN_18") (pintype "bidirectional"))
      (node (ref "U3") (pin "18") (pinfunction "USB_DN_18") (pintype "bidirectional"))
    )
    (net (code "84") (name "USB_DP") (class "Default")
      (node (ref "U2") (pin "16") (pinfunction "USB_DP_16") (pintype "bidirectional"))
      (node (ref "U3") (pin "16") (pinfunction "USB_DP_16") (pintype "bidirectional"))
    )
    (net (code "85") (name "USB_ID") (class "Default")
      (node (ref "U2") (pin "3") (pinfunction "USB_ID_3") (pintype "bidirectional"))
      (node (ref "U3") (pin "3") (pinfunction "USB_ID_3") (pintype "bidirectional"))
    )
    (net (code "86") (name "USB_VBUS") (class "Default")
      (node (ref "U2") (pin "20") (pinfunction "USB_VBUS_20") (pintype "bidirectional"))
      (node (ref "U3") (pin "20") (pinfunction "USB_VBUS_20") (pintype "bidirectional"))
    )
    (net (code "87") (name "VSYS") (class "Default")
      (node (ref "C8") (pin "1") (pinfunction "1_1") (pintype "passive"))
      (node (ref "C9") (pin "1") (pinfunction "1_1") (pintype "passive"))
      (node (ref "D1") (pin "A") (pinfunction "A_A") (pintype "passive"))
      (node (ref "D3") (pin "A") (pinfunction "A_A") (pintype "passive"))
      (node (ref "L1") (pin "P$2") (pinfunction "2_P$2") (pintype "passive"))
      (node (ref "Q1") (pin "3") (pinfunction "D_3") (pintype "passive"))
      (node (ref "R7") (pin "2") (pinfunction "2_2") (pintype "passive"))
      (node (ref "R9") (pin "1") (pinfunction "1_1") (pintype "passive"))
      (node (ref "U2") (pin "2") (pinfunction "VSYS_2") (pintype "bidirectional"))
      (node (ref "U2") (pin "4") (pinfunction "VSYS_4") (pintype "bidirectional"))
      (node (ref "U2") (pin "6") (pinfunction "VSYS_6") (pintype "bidirectional"))
      (node (ref "U3") (pin "2") (pinfunction "VSYS_2") (pintype "bidirectional"))
      (node (ref "U3") (pin "4") (pinfunction "VSYS_4") (pintype "bidirectional"))
      (node (ref "U3") (pin "6") (pinfunction "VSYS_6") (pintype "bidirectional"))
      (node (ref "U5") (pin "1") (pinfunction "IN_1") (pintype "input"))
      (node (ref "U5") (pin "3") (pinfunction "EN_3") (pintype "input"))
    )
    (net (code "88") (name "V_BAT_BKUP") (class "Default")
      (node (ref "U2") (pin "23") (pinfunction "V_VAT_BKUP_23") (pintype "bidirectional"))
      (node (ref "U3") (pin "23") (pinfunction "V_VAT_BKUP_23") (pintype "bidirectional"))
    )
    (net (code "89") (name "unconnected-(JP3-D+-PadD+1)") (class "Default")
      (node (ref "JP3") (pin "D+1") (pinfunction "D+_D+1") (pintype "bidirectional"))
    )
    (net (code "90") (name "unconnected-(JP3-D--PadD-1)") (class "Default")
      (node (ref "JP3") (pin "D-1") (pinfunction "D-_D-1") (pintype "bidirectional"))
    )
    (net (code "91") (name "unconnected-(JP3-ID-PadID1)") (class "Default")
      (node (ref "JP3") (pin "ID1") (pinfunction "ID_ID1") (pintype "bidirectional"))
    )
    (net (code "92") (name "unconnected-(U5-BP-Pad4)") (class "Default")
      (node (ref "U5") (pin "4") (pinfunction "BP_4") (pintype "input"))
    )
    (net (code "93") (name "unconnected-(U7-A8-Pad10)") (class "Default")
      (node (ref "U7") (pin "10") (pinfunction "A8_10") (pintype "bidirectional"))
    )
    (net (code "94") (name "unconnected-(U7-B8-Pad11)") (class "Default")
      (node (ref "U7") (pin "11") (pinfunction "B8_11") (pintype "bidirectional"))
    )
  )
)
